# SH2_-_CONNECTORS_1.net
KiCad netlist of a schematic drawn in Altium Designer
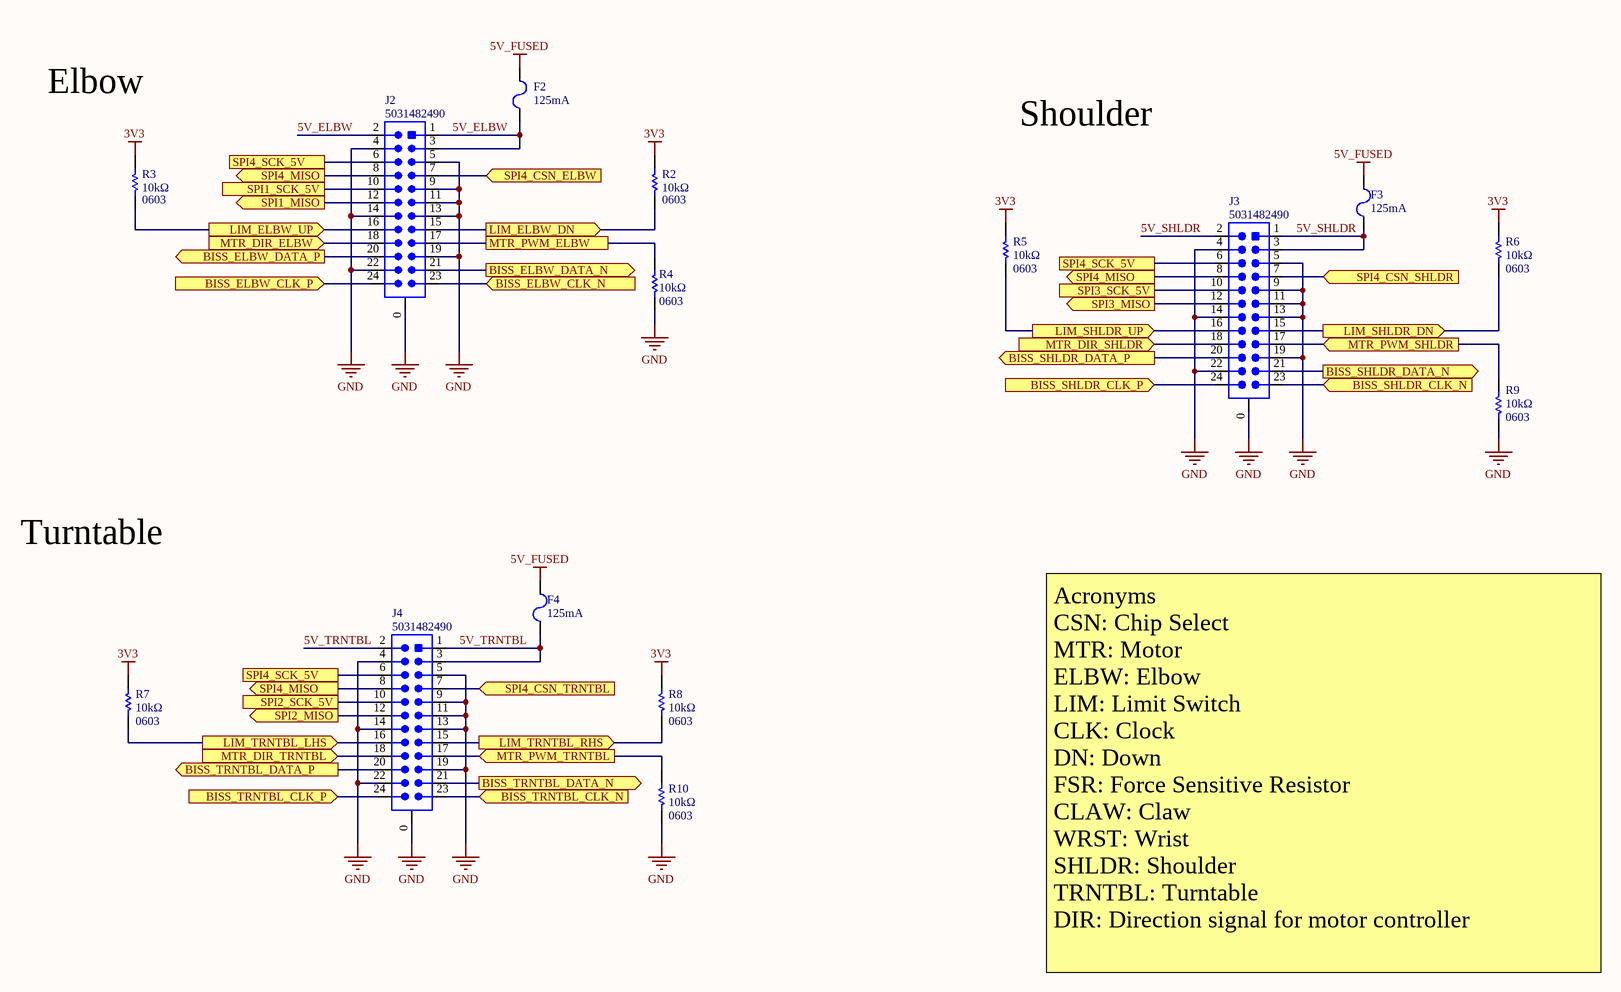
[diagram p0: SH2 - CONNECTORS_1.SchDoc]

(export (version "E")
  (design (tool "Eeschema 10.0.6"))
  (components
    (comp (ref "F2")
      (value "FUSE_125mA_1206")
      (footprint "FUSE_1206")
      (description "FUSE BOARD MNT 125MA 125VAC/VDC")
      (fields (field (name "CURRENT RATING") "125mA"))
      (libsource (lib "UWRT_Schematic_Library_2020") (part "FUSE_125mA_1206"))
    )
    (comp (ref "F3")
      (value "FUSE_125mA_1206")
      (footprint "FUSE_1206")
      (description "FUSE BOARD MNT 125MA 125VAC/VDC")
      (fields (field (name "CURRENT RATING") "125mA"))
      (libsource (lib "UWRT_Schematic_Library_2020") (part "FUSE_125mA_1206"))
    )
    (comp (ref "F4")
      (value "FUSE_125mA_1206")
      (footprint "FUSE_1206")
      (description "FUSE BOARD MNT 125MA 125VAC/VDC")
      (fields (field (name "CURRENT RATING") "125mA"))
      (libsource (lib "UWRT_Schematic_Library_2020") (part "FUSE_125mA_1206"))
    )
    (comp (ref "J2")
      (value "CON_12x2M_SM_RA")
      (footprint "MOLEX-5031482490")
      (description "CONN HEADER SMD RIGHT ANGLE 1.5MM PITCH")
      (fields (field (name "MANUFACTURER PART NUMBER 1") "5031482490"))
      (libsource (lib "UWRT_Schematic_Library_2020") (part "CON_12x2M_SM_RA"))
    )
    (comp (ref "J3")
      (value "CON_12x2M_SM_RA")
      (footprint "MOLEX-5031482490")
      (description "CONN HEADER SMD RIGHT ANGLE 1.5MM PITCH")
      (fields (field (name "MANUFACTURER PART NUMBER 1") "5031482490"))
      (libsource (lib "UWRT_Schematic_Library_2020") (part "CON_12x2M_SM_RA"))
    )
    (comp (ref "J4")
      (value "CON_12x2M_SM_RA")
      (footprint "MOLEX-5031482490")
      (description "CONN HEADER SMD RIGHT ANGLE 1.5MM PITCH")
      (fields (field (name "MANUFACTURER PART NUMBER 1") "5031482490"))
      (libsource (lib "UWRT_Schematic_Library_2020") (part "CON_12x2M_SM_RA"))
    )
    (comp (ref "R2")
      (value "10kΩ")
      (footprint "RESC0603")
      (description "RES 10K OHM 5% 1/10W 0603")
      (fields (field (name "PACKAGE/FOOTPRINT") "0603") (field (name "Comment") "RES_10kΩ_0603_5%"))
      (libsource (lib "UWRT_Schematic_Library_2020") (part "RES_10kΩ_0603_5%"))
    )
    (comp (ref "R3")
      (value "10kΩ")
      (footprint "RESC0603")
      (description "RES 10K OHM 5% 1/10W 0603")
      (fields (field (name "PACKAGE/FOOTPRINT") "0603") (field (name "Comment") "RES_10kΩ_0603_5%"))
      (libsource (lib "UWRT_Schematic_Library_2020") (part "RES_10kΩ_0603_5%"))
    )
    (comp (ref "R4")
      (value "10kΩ")
      (footprint "RESC0603")
      (description "RES 10K OHM 5% 1/10W 0603")
      (fields (field (name "PACKAGE/FOOTPRINT") "0603") (field (name "Comment") "RES_10kΩ_0603_5%"))
      (libsource (lib "UWRT_Schematic_Library_2020") (part "RES_10kΩ_0603_5%"))
    )
    (comp (ref "R5")
      (value "10kΩ")
      (footprint "RESC0603")
      (description "RES 10K OHM 5% 1/10W 0603")
      (fields (field (name "PACKAGE/FOOTPRINT") "0603") (field (name "Comment") "RES_10kΩ_0603_5%"))
      (libsource (lib "UWRT_Schematic_Library_2020") (part "RES_10kΩ_0603_5%"))
    )
    (comp (ref "R6")
      (value "10kΩ")
      (footprint "RESC0603")
      (description "RES 10K OHM 5% 1/10W 0603")
      (fields (field (name "PACKAGE/FOOTPRINT") "0603") (field (name "Comment") "RES_10kΩ_0603_5%"))
      (libsource (lib "UWRT_Schematic_Library_2020") (part "RES_10kΩ_0603_5%"))
    )
    (comp (ref "R7")
      (value "10kΩ")
      (footprint "RESC0603")
      (description "RES 10K OHM 5% 1/10W 0603")
      (fields (field (name "PACKAGE/FOOTPRINT") "0603") (field (name "Comment") "RES_10kΩ_0603_5%"))
      (libsource (lib "UWRT_Schematic_Library_2020") (part "RES_10kΩ_0603_5%"))
    )
    (comp (ref "R8")
      (value "10kΩ")
      (footprint "RESC0603")
      (description "RES 10K OHM 5% 1/10W 0603")
      (fields (field (name "PACKAGE/FOOTPRINT") "0603") (field (name "Comment") "RES_10kΩ_0603_5%"))
      (libsource (lib "UWRT_Schematic_Library_2020") (part "RES_10kΩ_0603_5%"))
    )
    (comp (ref "R9")
      (value "10kΩ")
      (footprint "RESC0603")
      (description "RES 10K OHM 5% 1/10W 0603")
      (fields (field (name "PACKAGE/FOOTPRINT") "0603") (field (name "Comment") "RES_10kΩ_0603_5%"))
      (libsource (lib "UWRT_Schematic_Library_2020") (part "RES_10kΩ_0603_5%"))
    )
    (comp (ref "R10")
      (value "10kΩ")
      (footprint "RESC0603")
      (description "RES 10K OHM 5% 1/10W 0603")
      (fields (field (name "PACKAGE/FOOTPRINT") "0603") (field (name "Comment") "RES_10kΩ_0603_5%"))
      (libsource (lib "UWRT_Schematic_Library_2020") (part "RES_10kΩ_0603_5%"))
    )
  )
  (nets
    (net (code "1") (name "/5V_ELBW") (class "Default")
      (node (ref "F2") (pin "1") (pinfunction "1_1") (pintype "passive"))
      (node (ref "J2") (pin "1") (pinfunction "1_1") (pintype "passive"))
      (node (ref "J2") (pin "2") (pinfunction "2_2") (pintype "passive"))
      (node (ref "J2") (pin "3") (pinfunction "3_3") (pintype "passive"))
    )
    (net (code "2") (name "/5V_SHLDR") (class "Default")
      (node (ref "F3") (pin "1") (pinfunction "1_1") (pintype "passive"))
      (node (ref "J3") (pin "1") (pinfunction "1_1") (pintype "passive"))
      (node (ref "J3") (pin "2") (pinfunction "2_2") (pintype "passive"))
      (node (ref "J3") (pin "3") (pinfunction "3_3") (pintype "passive"))
    )
    (net (code "3") (name "/5V_TRNTBL") (class "Default")
      (node (ref "F4") (pin "1") (pinfunction "1_1") (pintype "passive"))
      (node (ref "J4") (pin "1") (pinfunction "1_1") (pintype "passive"))
      (node (ref "J4") (pin "2") (pinfunction "2_2") (pintype "passive"))
      (node (ref "J4") (pin "3") (pinfunction "3_3") (pintype "passive"))
    )
    (net (code "4") (name "/BISS_ELBW_CLK_N") (class "Default")
      (node (ref "J2") (pin "23") (pinfunction "23_23") (pintype "passive"))
    )
    (net (code "5") (name "/BISS_ELBW_CLK_P") (class "Default")
      (node (ref "J2") (pin "24") (pinfunction "24_24") (pintype "passive"))
    )
    (net (code "6") (name "/BISS_ELBW_DATA_N") (class "Default")
      (node (ref "J2") (pin "21") (pinfunction "21_21") (pintype "passive"))
    )
    (net (code "7") (name "/BISS_ELBW_DATA_P") (class "Default")
      (node (ref "J2") (pin "20") (pinfunction "20_20") (pintype "passive"))
    )
    (net (code "8") (name "/BISS_SHLDR_CLK_N") (class "Default")
      (node (ref "J3") (pin "23") (pinfunction "23_23") (pintype "passive"))
    )
    (net (code "9") (name "/BISS_SHLDR_CLK_P") (class "Default")
      (node (ref "J3") (pin "24") (pinfunction "24_24") (pintype "passive"))
    )
    (net (code "10") (name "/BISS_SHLDR_DATA_N") (class "Default")
      (node (ref "J3") (pin "21") (pinfunction "21_21") (pintype "passive"))
    )
    (net (code "11") (name "/BISS_SHLDR_DATA_P") (class "Default")
      (node (ref "J3") (pin "20") (pinfunction "20_20") (pintype "passive"))
    )
    (net (code "12") (name "/BISS_TRNTBL_CLK_N") (class "Default")
      (node (ref "J4") (pin "23") (pinfunction "23_23") (pintype "passive"))
    )
    (net (code "13") (name "/BISS_TRNTBL_CLK_P") (class "Default")
      (node (ref "J4") (pin "24") (pinfunction "24_24") (pintype "passive"))
    )
    (net (code "14") (name "/BISS_TRNTBL_DATA_N") (class "Default")
      (node (ref "J4") (pin "21") (pinfunction "21_21") (pintype "passive"))
    )
    (net (code "15") (name "/BISS_TRNTBL_DATA_P") (class "Default")
      (node (ref "J4") (pin "20") (pinfunction "20_20") (pintype "passive"))
    )
    (net (code "16") (name "/LIM_ELBW_DN") (class "Default")
      (node (ref "J2") (pin "15") (pinfunction "15_15") (pintype "passive"))
      (node (ref "R2") (pin "1") (pinfunction "1_1") (pintype "passive"))
    )
    (net (code "17") (name "/LIM_ELBW_UP") (class "Default")
      (node (ref "J2") (pin "16") (pinfunction "16_16") (pintype "passive"))
      (node (ref "R3") (pin "1") (pinfunction "1_1") (pintype "passive"))
    )
    (net (code "18") (name "/LIM_SHLDR_DN") (class "Default")
      (node (ref "J3") (pin "15") (pinfunction "15_15") (pintype "passive"))
      (node (ref "R6") (pin "1") (pinfunction "1_1") (pintype "passive"))
    )
    (net (code "19") (name "/LIM_SHLDR_UP") (class "Default")
      (node (ref "J3") (pin "16") (pinfunction "16_16") (pintype "passive"))
      (node (ref "R5") (pin "1") (pinfunction "1_1") (pintype "passive"))
    )
    (net (code "20") (name "/LIM_TRNTBL_LHS") (class "Default")
      (node (ref "J4") (pin "16") (pinfunction "16_16") (pintype "passive"))
      (node (ref "R7") (pin "1") (pinfunction "1_1") (pintype "passive"))
    )
    (net (code "21") (name "/LIM_TRNTBL_RHS") (class "Default")
      (node (ref "J4") (pin "15") (pinfunction "15_15") (pintype "passive"))
      (node (ref "R8") (pin "1") (pinfunction "1_1") (pintype "passive"))
    )
    (net (code "22") (name "/MTR_DIR_ELBW") (class "Default")
      (node (ref "J2") (pin "18") (pinfunction "18_18") (pintype "passive"))
    )
    (net (code "23") (name "/MTR_DIR_SHLDR") (class "Default")
      (node (ref "J3") (pin "18") (pinfunction "18_18") (pintype "passive"))
    )
    (net (code "24") (name "/MTR_DIR_TRNTBL") (class "Default")
      (node (ref "J4") (pin "18") (pinfunction "18_18") (pintype "passive"))
    )
    (net (code "25") (name "/MTR_PWM_ELBW") (class "Default")
      (node (ref "J2") (pin "17") (pinfunction "17_17") (pintype "passive"))
      (node (ref "R4") (pin "2") (pinfunction "2_2") (pintype "passive"))
    )
    (net (code "26") (name "/MTR_PWM_SHLDR") (class "Default")
      (node (ref "J3") (pin "17") (pinfunction "17_17") (pintype "passive"))
      (node (ref "R9") (pin "2") (pinfunction "2_2") (pintype "passive"))
    )
    (net (code "27") (name "/MTR_PWM_TRNTBL") (class "Default")
      (node (ref "J4") (pin "17") (pinfunction "17_17") (pintype "passive"))
      (node (ref "R10") (pin "2") (pinfunction "2_2") (pintype "passive"))
    )
    (net (code "28") (name "/SPI1_MISO") (class "Default")
      (node (ref "J2") (pin "12") (pinfunction "12_12") (pintype "passive"))
    )
    (net (code "29") (name "/SPI1_SCK_5V") (class "Default")
      (node (ref "J2") (pin "10") (pinfunction "10_10") (pintype "passive"))
    )
    (net (code "30") (name "/SPI2_MISO") (class "Default")
      (node (ref "J4") (pin "12") (pinfunction "12_12") (pintype "passive"))
    )
    (net (code "31") (name "/SPI2_SCK_5V") (class "Default")
      (node (ref "J4") (pin "10") (pinfunction "10_10") (pintype "passive"))
    )
    (net (code "32") (name "/SPI3_MISO") (class "Default")
      (node (ref "J3") (pin "12") (pinfunction "12_12") (pintype "passive"))
    )
    (net (code "33") (name "/SPI3_SCK_5V") (class "Default")
      (node (ref "J3") (pin "10") (pinfunction "10_10") (pintype "passive"))
    )
    (net (code "34") (name "/SPI4_CSN_ELBW") (class "Default")
      (node (ref "J2") (pin "7") (pinfunction "7_7") (pintype "passive"))
    )
    (net (code "35") (name "/SPI4_CSN_SHLDR") (class "Default")
      (node (ref "J3") (pin "7") (pinfunction "7_7") (pintype "passive"))
    )
    (net (code "36") (name "/SPI4_CSN_TRNTBL") (class "Default")
      (node (ref "J4") (pin "7") (pinfunction "7_7") (pintype "passive"))
    )
    (net (code "37") (name "/SPI4_MISO") (class "Default")
      (node (ref "J2") (pin "8") (pinfunction "8_8") (pintype "passive"))
      (node (ref "J3") (pin "8") (pinfunction "8_8") (pintype "passive"))
      (node (ref "J4") (pin "8") (pinfunction "8_8") (pintype "passive"))
    )
    (net (code "38") (name "/SPI4_SCK_5V") (class "Default")
      (node (ref "J2") (pin "6") (pinfunction "6_6") (pintype "passive"))
      (node (ref "J3") (pin "6") (pinfunction "6_6") (pintype "passive"))
      (node (ref "J4") (pin "6") (pinfunction "6_6") (pintype "passive"))
    )
    (net (code "39") (name "3V3") (class "Default")
      (node (ref "R2") (pin "2") (pinfunction "2_2") (pintype "passive"))
      (node (ref "R3") (pin "2") (pinfunction "2_2") (pintype "passive"))
      (node (ref "R5") (pin "2") (pinfunction "2_2") (pintype "passive"))
      (node (ref "R6") (pin "2") (pinfunction "2_2") (pintype "passive"))
      (node (ref "R7") (pin "2") (pinfunction "2_2") (pintype "passive"))
      (node (ref "R8") (pin "2") (pinfunction "2_2") (pintype "passive"))
    )
    (net (code "40") (name "5V_FUSED") (class "Default")
      (node (ref "F2") (pin "2") (pinfunction "2_2") (pintype "passive"))
      (node (ref "F3") (pin "2") (pinfunction "2_2") (pintype "passive"))
      (node (ref "F4") (pin "2") (pinfunction "2_2") (pintype "passive"))
    )
    (net (code "41") (name "GND") (class "Default")
      (node (ref "J2") (pin "0") (pinfunction "0_0") (pintype "passive"))
      (node (ref "J2") (pin "11") (pinfunction "11_11") (pintype "passive"))
      (node (ref "J2") (pin "13") (pinfunction "13_13") (pintype "passive"))
      (node (ref "J2") (pin "14") (pinfunction "14_14") (pintype "passive"))
      (node (ref "J2") (pin "19") (pinfunction "19_19") (pintype "passive"))
      (node (ref "J2") (pin "22") (pinfunction "22_22") (pintype "passive"))
      (node (ref "J2") (pin "4") (pinfunction "4_4") (pintype "passive"))
      (node (ref "J2") (pin "5") (pinfunction "5_5") (pintype "passive"))
      (node (ref "J2") (pin "9") (pinfunction "9_9") (pintype "passive"))
      (node (ref "J3") (pin "0") (pinfunction "0_0") (pintype "passive"))
      (node (ref "J3") (pin "11") (pinfunction "11_11") (pintype "passive"))
      (node (ref "J3") (pin "13") (pinfunction "13_13") (pintype "passive"))
      (node (ref "J3") (pin "14") (pinfunction "14_14") (pintype "passive"))
      (node (ref "J3") (pin "19") (pinfunction "19_19") (pintype "passive"))
      (node (ref "J3") (pin "22") (pinfunction "22_22") (pintype "passive"))
      (node (ref "J3") (pin "4") (pinfunction "4_4") (pintype "passive"))
      (node (ref "J3") (pin "5") (pinfunction "5_5") (pintype "passive"))
      (node (ref "J3") (pin "9") (pinfunction "9_9") (pintype "passive"))
      (node (ref "J4") (pin "0") (pinfunction "0_0") (pintype "passive"))
      (node (ref "J4") (pin "11") (pinfunction "11_11") (pintype "passive"))
      (node (ref "J4") (pin "13") (pinfunction "13_13") (pintype "passive"))
      (node (ref "J4") (pin "14") (pinfunction "14_14") (pintype "passive"))
      (node (ref "J4") (pin "19") (pinfunction "19_19") (pintype "passive"))
      (node (ref "J4") (pin "22") (pinfunction "22_22") (pintype "passive"))
      (node (ref "J4") (pin "4") (pinfunction "4_4") (pintype "passive"))
      (node (ref "J4") (pin "5") (pinfunction "5_5") (pintype "passive"))
      (node (ref "J4") (pin "9") (pinfunction "9_9") (pintype "passive"))
      (node (ref "R10") (pin "1") (pinfunction "1_1") (pintype "passive"))
      (node (ref "R4") (pin "1") (pinfunction "1_1") (pintype "passive"))
      (node (ref "R9") (pin "1") (pinfunction "1_1") (pintype "passive"))
    )
  )
)
